# CODEC.net
KiCad netlist of a schematic drawn in Altium Designer
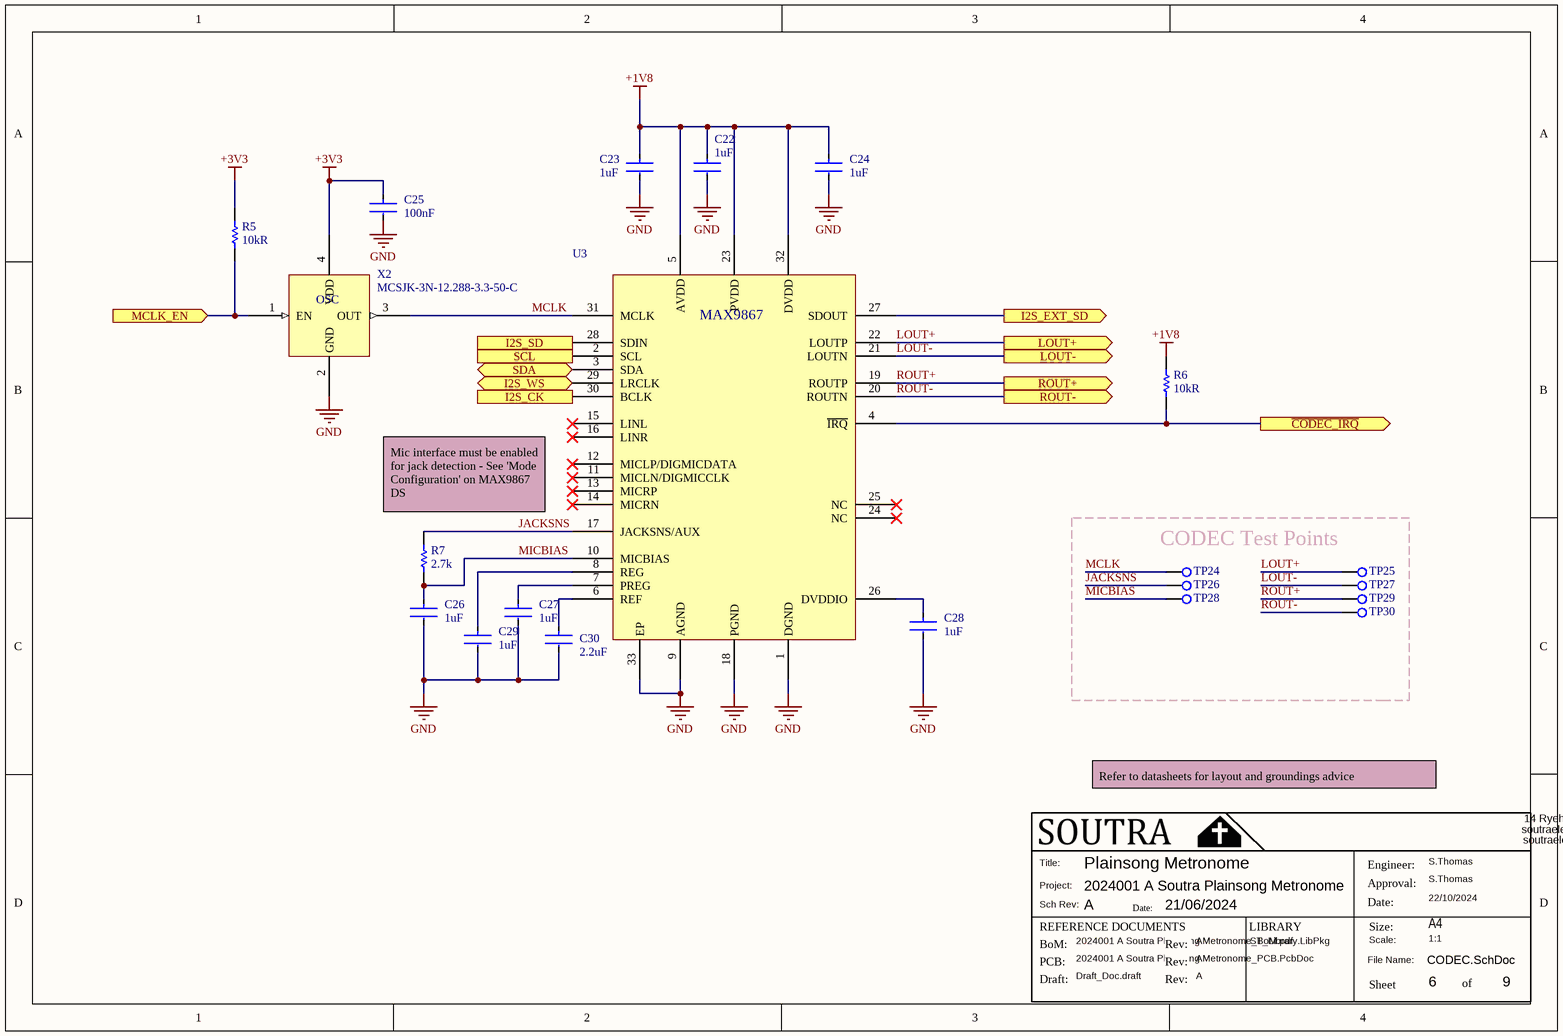
[diagram p0: CODEC.SchDoc]

(export (version "E")
  (design (tool "Eeschema 10.0.6"))
  (components
    (comp (ref "C22")
      (value "1uF")
      (footprint "CAPC1005X06L")
      (fields
        (field (name "MANUFACTURER") "Yageo")
        (field (name "MANUFACTURER PART NUMBER") "CC0402KRX5R6BB105")
        (field (name "ALTERNATIVE PART") "0402ZD105KAT2A")
      )
      (libsource (lib "ST_Library") (part "CC0402KRX5R6BB105"))
    )
    (comp (ref "C23")
      (value "1uF")
      (footprint "CAPC1005X06L")
      (fields
        (field (name "MANUFACTURER") "Yageo")
        (field (name "MANUFACTURER PART NUMBER") "CC0402KRX5R6BB105")
        (field (name "ALTERNATIVE PART") "0402ZD105KAT2A")
      )
      (libsource (lib "ST_Library") (part "CC0402KRX5R6BB105"))
    )
    (comp (ref "C24")
      (value "1uF")
      (footprint "CAPC1005X06L")
      (fields
        (field (name "MANUFACTURER") "Yageo")
        (field (name "MANUFACTURER PART NUMBER") "CC0402KRX5R6BB105")
        (field (name "ALTERNATIVE PART") "0402ZD105KAT2A")
      )
      (libsource (lib "ST_Library") (part "CC0402KRX5R6BB105"))
    )
    (comp (ref "C25")
      (value "100nF")
      (footprint "CAPC1005X06L")
      (fields
        (field (name "MANUFACTURER") "Walsin Technologies")
        (field (name "MANUFACTURER PART NUMBER") "0402X104M160CT")
        (field (name "ALTERNATIVE PART") "885012105016")
      )
      (libsource (lib "ST_Library") (part "0402X104M160CT"))
    )
    (comp (ref "C26")
      (value "1uF")
      (footprint "CAPC1005X06L")
      (fields
        (field (name "MANUFACTURER") "Yageo")
        (field (name "MANUFACTURER PART NUMBER") "CC0402KRX5R6BB105")
        (field (name "ALTERNATIVE PART") "0402ZD105KAT2A")
      )
      (libsource (lib "ST_Library") (part "CC0402KRX5R6BB105"))
    )
    (comp (ref "C27")
      (value "1uF")
      (footprint "CAPC1005X06L")
      (fields
        (field (name "MANUFACTURER") "Yageo")
        (field (name "MANUFACTURER PART NUMBER") "CC0402KRX5R6BB105")
        (field (name "ALTERNATIVE PART") "0402ZD105KAT2A")
      )
      (libsource (lib "ST_Library") (part "CC0402KRX5R6BB105"))
    )
    (comp (ref "C28")
      (value "1uF")
      (footprint "CAPC1005X06L")
      (fields
        (field (name "MANUFACTURER") "Yageo")
        (field (name "MANUFACTURER PART NUMBER") "CC0402KRX5R6BB105")
        (field (name "ALTERNATIVE PART") "0402ZD105KAT2A")
      )
      (libsource (lib "ST_Library") (part "CC0402KRX5R6BB105"))
    )
    (comp (ref "C29")
      (value "1uF")
      (footprint "CAPC1005X06L")
      (fields
        (field (name "MANUFACTURER") "Yageo")
        (field (name "MANUFACTURER PART NUMBER") "CC0402KRX5R6BB105")
        (field (name "ALTERNATIVE PART") "0402ZD105KAT2A")
      )
      (libsource (lib "ST_Library") (part "CC0402KRX5R6BB105"))
    )
    (comp (ref "C30")
      (value "2.2uF")
      (footprint "CAPC1005X06L")
      (fields
        (field (name "MANUFACTURER") "Yageo")
        (field (name "MANUFACTURER PART NUMBER") "CC0402MRX5R5BB225")
        (field (name "ALTERNATIVE PART") "MC0402X225M6R3CT")
      )
      (libsource (lib "ST_Library") (part "CC0402MRX5R5BB225"))
    )
    (comp (ref "R5")
      (value "10kR")
      (footprint "RESC_0805_2013X50X30LL20T20")
      (fields
        (field (name "MANUFACTURER") "Yageo")
        (field (name "MANUFACTURER PART NUMBER") "RC0805JR-0710KL")
        (field (name "TOLERANCE") "5%")
      )
      (libsource (lib "ST_Library") (part "RC0805JR-0710KL"))
    )
    (comp (ref "R6")
      (value "10kR")
      (footprint "RESC_0805_2013X50X30LL20T20")
      (fields
        (field (name "MANUFACTURER") "Yageo")
        (field (name "MANUFACTURER PART NUMBER") "RC0805JR-0710KL")
        (field (name "TOLERANCE") "5%")
      )
      (libsource (lib "ST_Library") (part "RC0805JR-0710KL"))
    )
    (comp (ref "R7")
      (value "2.7k")
      (footprint "RESC_0805_2013X50X30LL20T20")
      (fields
        (field (name "MANUFACTURER") "TE Connectivity")
        (field (name "MANUFACTURER PART NUMBER") "CRGH0805F2K7")
        (field (name "ALTERNATIVE PART") "MC01W08051100R")
      )
      (libsource (lib "ST_Library") (part "CRGH0805F2K7"))
    )
    (comp (ref "TP24")
      (value "TP_CIRCLE_R1")
      (footprint "TP_CIRCLE_R1")
      (description "Test Point, SMD, Circular, Radius = 1mm")
      (libsource (lib "ST_Library") (part "TP_CIRCLE_R1"))
    )
    (comp (ref "TP25")
      (value "TP_CIRCLE_R1")
      (footprint "TP_CIRCLE_R1")
      (description "Test Point, SMD, Circular, Radius = 1mm")
      (libsource (lib "ST_Library") (part "TP_CIRCLE_R1"))
    )
    (comp (ref "TP26")
      (value "TP_CIRCLE_R1")
      (footprint "TP_CIRCLE_R1")
      (description "Test Point, SMD, Circular, Radius = 1mm")
      (libsource (lib "ST_Library") (part "TP_CIRCLE_R1"))
    )
    (comp (ref "TP27")
      (value "TP_CIRCLE_R1")
      (footprint "TP_CIRCLE_R1")
      (description "Test Point, SMD, Circular, Radius = 1mm")
      (libsource (lib "ST_Library") (part "TP_CIRCLE_R1"))
    )
    (comp (ref "TP28")
      (value "TP_CIRCLE_R1")
      (footprint "TP_CIRCLE_R1")
      (description "Test Point, SMD, Circular, Radius = 1mm")
      (libsource (lib "ST_Library") (part "TP_CIRCLE_R1"))
    )
    (comp (ref "TP29")
      (value "TP_CIRCLE_R1")
      (footprint "TP_CIRCLE_R1")
      (description "Test Point, SMD, Circular, Radius = 1mm")
      (libsource (lib "ST_Library") (part "TP_CIRCLE_R1"))
    )
    (comp (ref "TP30")
      (value "TP_CIRCLE_R1")
      (footprint "TP_CIRCLE_R1")
      (description "Test Point, SMD, Circular, Radius = 1mm")
      (libsource (lib "ST_Library") (part "TP_CIRCLE_R1"))
    )
    (comp (ref "U3")
      (value "~")
      (footprint "TQFN50P500X500X80_HS-33L")
      (description "PCM Codec")
      (fields (field (name "MANUFACTURER") "Maxim") (field (name "MANUFACTURER PART NUMBER") "MAX9867ETJ+T"))
      (libsource (lib "ST_Library") (part "MAX9867ETJ+T"))
    )
    (comp (ref "X2")
      (value "MCSJK-3N-12.288-3.3-50-C")
      (footprint "X_MULTICOMP_MCSJK-3N-12.288-3.3-50-C")
      (description "CMOS Output Clock Oscillator")
      (fields (field (name "MANUFACTURER") "Multicomp"))
      (libsource (lib "ST_Library") (part "MCSJK-3N-12.288-3.3-50-C"))
    )
  )
  (nets
    (net (code "1") (name "+1V8") (class "Default")
      (node (ref "C22") (pin "1") (pinfunction "1_1") (pintype "passive"))
      (node (ref "C23") (pin "1") (pinfunction "1_1") (pintype "passive"))
      (node (ref "C24") (pin "1") (pinfunction "1_1") (pintype "passive"))
      (node (ref "R6") (pin "2") (pinfunction "2_2") (pintype "passive"))
      (node (ref "U3") (pin "23") (pinfunction "PVDD_23") (pintype "passive"))
      (node (ref "U3") (pin "32") (pinfunction "DVDD_32") (pintype "passive"))
      (node (ref "U3") (pin "5") (pinfunction "AVDD_5") (pintype "passive"))
    )
    (net (code "2") (name "+3V3") (class "Default")
      (node (ref "C25") (pin "1") (pinfunction "1_1") (pintype "passive"))
      (node (ref "R5") (pin "2") (pinfunction "2_2") (pintype "passive"))
      (node (ref "X2") (pin "4") (pinfunction "VDD_4") (pintype "passive"))
    )
    (net (code "3") (name "/I2S_CK") (class "Default")
      (node (ref "U3") (pin "30") (pinfunction "BCLK_30") (pintype "passive"))
    )
    (net (code "4") (name "/I2S_EXT_SD") (class "Default")
      (node (ref "U3") (pin "27") (pinfunction "SDOUT_27") (pintype "passive"))
    )
    (net (code "5") (name "/I2S_SD") (class "Default")
      (node (ref "U3") (pin "28") (pinfunction "SDIN_28") (pintype "passive"))
    )
    (net (code "6") (name "/I2S_WS") (class "Default")
      (node (ref "U3") (pin "29") (pinfunction "LRCLK_29") (pintype "passive"))
    )
    (net (code "7") (name "/JACKSNS") (class "Default")
      (node (ref "R7") (pin "1") (pinfunction "1_1") (pintype "passive"))
      (node (ref "TP26") (pin "1") (pinfunction "1_1") (pintype "passive"))
      (node (ref "U3") (pin "17") (pinfunction "JACKSNS/AUX_17") (pintype "passive"))
    )
    (net (code "8") (name "/LOUT+") (class "Default")
      (node (ref "TP25") (pin "1") (pinfunction "1_1") (pintype "passive"))
      (node (ref "U3") (pin "22") (pinfunction "LOUTP_22") (pintype "passive"))
    )
    (net (code "9") (name "/LOUT-") (class "Default")
      (node (ref "TP27") (pin "1") (pinfunction "1_1") (pintype "passive"))
      (node (ref "U3") (pin "21") (pinfunction "LOUTN_21") (pintype "passive"))
    )
    (net (code "10") (name "/MCLK") (class "Default")
      (node (ref "TP24") (pin "1") (pinfunction "1_1") (pintype "passive"))
      (node (ref "U3") (pin "31") (pinfunction "MCLK_31") (pintype "passive"))
      (node (ref "X2") (pin "3") (pinfunction "OUT_3") (pintype "output"))
    )
    (net (code "11") (name "/MCLK_EN") (class "Default")
      (node (ref "R5") (pin "1") (pinfunction "1_1") (pintype "passive"))
      (node (ref "X2") (pin "1") (pinfunction "EN_1") (pintype "input"))
    )
    (net (code "12") (name "/MICBIAS") (class "Default")
      (node (ref "C26") (pin "1") (pinfunction "1_1") (pintype "passive"))
      (node (ref "R7") (pin "2") (pinfunction "2_2") (pintype "passive"))
      (node (ref "TP28") (pin "1") (pinfunction "1_1") (pintype "passive"))
      (node (ref "U3") (pin "10") (pinfunction "MICBIAS_10") (pintype "passive"))
    )
    (net (code "13") (name "/ROUT+") (class "Default")
      (node (ref "TP29") (pin "1") (pinfunction "1_1") (pintype "passive"))
      (node (ref "U3") (pin "19") (pinfunction "ROUTP_19") (pintype "passive"))
    )
    (net (code "14") (name "/ROUT-") (class "Default")
      (node (ref "TP30") (pin "1") (pinfunction "1_1") (pintype "passive"))
      (node (ref "U3") (pin "20") (pinfunction "ROUTN_20") (pintype "passive"))
    )
    (net (code "15") (name "/SCL") (class "Default")
      (node (ref "U3") (pin "2") (pinfunction "SCL_2") (pintype "passive"))
    )
    (net (code "16") (name "/SDA") (class "Default")
      (node (ref "U3") (pin "3") (pinfunction "SDA_3") (pintype "passive"))
    )
    (net (code "17") (name "/~{CODEC_IRQ}") (class "Default")
      (node (ref "R6") (pin "1") (pinfunction "1_1") (pintype "passive"))
      (node (ref "U3") (pin "4") (pinfunction "~{IRQ}_4") (pintype "passive"))
    )
    (net (code "18") (name "GND") (class "Default")
      (node (ref "C22") (pin "2") (pinfunction "2_2") (pintype "passive"))
      (node (ref "C23") (pin "2") (pinfunction "2_2") (pintype "passive"))
      (node (ref "C24") (pin "2") (pinfunction "2_2") (pintype "passive"))
      (node (ref "C25") (pin "2") (pinfunction "2_2") (pintype "passive"))
      (node (ref "C26") (pin "2") (pinfunction "2_2") (pintype "passive"))
      (node (ref "C27") (pin "2") (pinfunction "2_2") (pintype "passive"))
      (node (ref "C28") (pin "2") (pinfunction "2_2") (pintype "passive"))
      (node (ref "C29") (pin "2") (pinfunction "2_2") (pintype "passive"))
      (node (ref "C30") (pin "2") (pinfunction "2_2") (pintype "passive"))
      (node (ref "U3") (pin "1") (pinfunction "DGND_1") (pintype "passive"))
      (node (ref "U3") (pin "18") (pinfunction "PGND_18") (pintype "passive"))
      (node (ref "U3") (pin "33") (pinfunction "EP_33") (pintype "passive"))
      (node (ref "U3") (pin "9") (pinfunction "AGND_9") (pintype "passive"))
      (node (ref "X2") (pin "2") (pinfunction "GND_2") (pintype "passive"))
    )
    (net (code "19") (name "Net-(U3-DVDDIO)") (class "Default")
      (node (ref "C28") (pin "1") (pinfunction "1_1") (pintype "passive"))
      (node (ref "U3") (pin "26") (pinfunction "DVDDIO_26") (pintype "passive"))
    )
    (net (code "20") (name "Net-(U3-PREG)") (class "Default")
      (node (ref "C27") (pin "1") (pinfunction "1_1") (pintype "passive"))
      (node (ref "U3") (pin "7") (pinfunction "PREG_7") (pintype "passive"))
    )
    (net (code "21") (name "Net-(U3-REF)") (class "Default")
      (node (ref "C30") (pin "1") (pinfunction "1_1") (pintype "passive"))
      (node (ref "U3") (pin "6") (pinfunction "REF_6") (pintype "passive"))
    )
    (net (code "22") (name "Net-(U3-REG)") (class "Default")
      (node (ref "C29") (pin "1") (pinfunction "1_1") (pintype "passive"))
      (node (ref "U3") (pin "8") (pinfunction "REG_8") (pintype "passive"))
    )
    (net (code "23") (name "unconnected-(U3-LINL-Pad15)") (class "Default")
      (node (ref "U3") (pin "15") (pinfunction "LINL_15") (pintype "passive+no_connect"))
    )
    (net (code "24") (name "unconnected-(U3-LINR-Pad16)") (class "Default")
      (node (ref "U3") (pin "16") (pinfunction "LINR_16") (pintype "passive+no_connect"))
    )
    (net (code "25") (name "unconnected-(U3-MICLN{slash}DIGMICCLK-Pad11)") (class "Default")
      (node (ref "U3") (pin "11") (pinfunction "MICLN/DIGMICCLK_11") (pintype "passive+no_connect"))
    )
    (net (code "26") (name "unconnected-(U3-MICLP{slash}DIGMICDATA-Pad12)") (class "Default")
      (node (ref "U3") (pin "12") (pinfunction "MICLP/DIGMICDATA_12") (pintype "passive+no_connect"))
    )
    (net (code "27") (name "unconnected-(U3-MICRN-Pad14)") (class "Default")
      (node (ref "U3") (pin "14") (pinfunction "MICRN_14") (pintype "passive+no_connect"))
    )
    (net (code "28") (name "unconnected-(U3-MICRP-Pad13)") (class "Default")
      (node (ref "U3") (pin "13") (pinfunction "MICRP_13") (pintype "passive+no_connect"))
    )
    (net (code "29") (name "unconnected-(U3-NC-Pad24)") (class "Default")
      (node (ref "U3") (pin "24") (pinfunction "NC_24") (pintype "passive+no_connect"))
    )
    (net (code "30") (name "unconnected-(U3-NC-Pad25)") (class "Default")
      (node (ref "U3") (pin "25") (pinfunction "NC_25") (pintype "passive+no_connect"))
    )
  )
)
